# 03_HLT.net
KiCad netlist of a schematic drawn in EAGLE
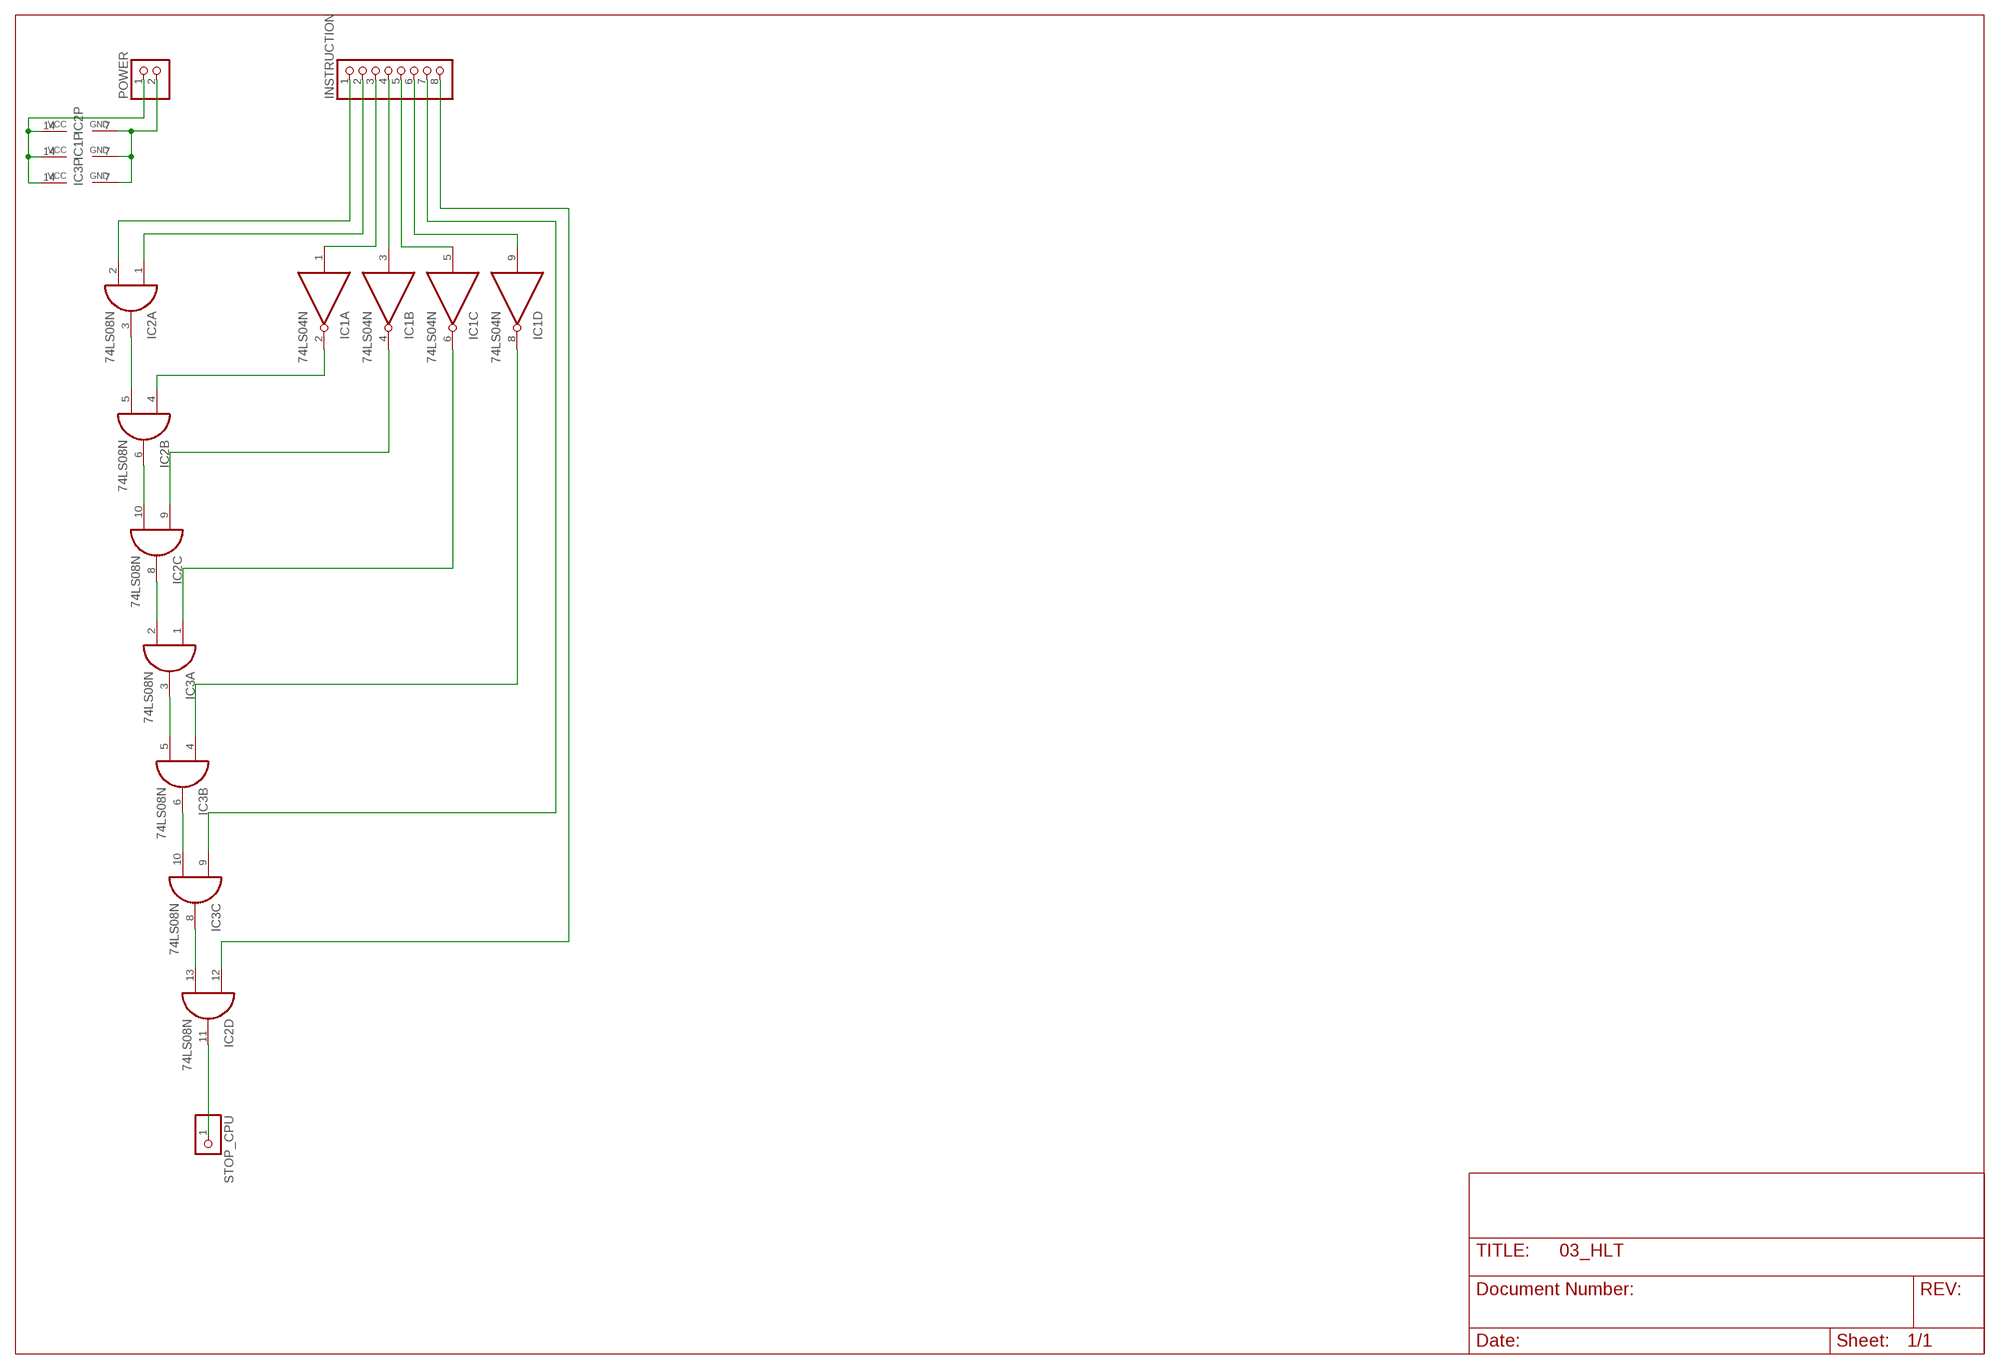
[diagram p0: schematic, sheet 1]

(export (version "E")
  (design (tool "Eeschema 10.0.6"))
  (components
    (comp (ref "IC1")
      (value "74LS04N")
      (footprint "eagle-import:DIL14")
      (libsource (lib "eagle-import") (part "7404NLS"))
    )
    (comp (ref "IC2")
      (value "74LS08N")
      (footprint "eagle-import:DIL14")
      (libsource (lib "eagle-import") (part "7408NLS"))
    )
    (comp (ref "IC3")
      (value "74LS08N")
      (footprint "eagle-import:DIL14")
      (libsource (lib "eagle-import") (part "7408NLS"))
    )
    (comp (ref "INSTRUCTION")
      (value "PINHD-1X8")
      (footprint "eagle-import:1X08")
      (libsource (lib "eagle-import") (part "PINHD-1X8"))
    )
    (comp (ref "POWER")
      (value "PINHD-1X2")
      (footprint "eagle-import:1X02")
      (libsource (lib "eagle-import") (part "PINHD-1X2"))
    )
    (comp (ref "STOP_CPU")
      (value "PINHD-1X1")
      (footprint "eagle-import:1X01")
      (libsource (lib "eagle-import") (part "PINHD-1X1"))
    )
  )
  (nets
    (net (code "1") (name "Net-(IC1A-I)") (class "Default")
      (node (ref "IC1") (pin "1") (pinfunction "I_1") (pintype "input"))
      (node (ref "INSTRUCTION") (pin "3") (pinfunction "3_3") (pintype "passive"))
    )
    (net (code "2") (name "Net-(IC1A-O)") (class "Default")
      (node (ref "IC1") (pin "2") (pinfunction "O_2") (pintype "output"))
      (node (ref "IC2") (pin "4") (pinfunction "I0_4") (pintype "input"))
    )
    (net (code "3") (name "Net-(IC1B-I)") (class "Default")
      (node (ref "IC1") (pin "3") (pinfunction "I_3") (pintype "input"))
      (node (ref "INSTRUCTION") (pin "4") (pinfunction "4_4") (pintype "passive"))
    )
    (net (code "4") (name "Net-(IC1B-O)") (class "Default")
      (node (ref "IC1") (pin "4") (pinfunction "O_4") (pintype "output"))
      (node (ref "IC2") (pin "9") (pinfunction "I0_9") (pintype "input"))
    )
    (net (code "5") (name "Net-(IC1C-I)") (class "Default")
      (node (ref "IC1") (pin "5") (pinfunction "I_5") (pintype "input"))
      (node (ref "INSTRUCTION") (pin "5") (pinfunction "5_5") (pintype "passive"))
    )
    (net (code "6") (name "Net-(IC1C-O)") (class "Default")
      (node (ref "IC1") (pin "6") (pinfunction "O_6") (pintype "output"))
      (node (ref "IC3") (pin "1") (pinfunction "I0_1") (pintype "input"))
    )
    (net (code "7") (name "Net-(IC1D-I)") (class "Default")
      (node (ref "IC1") (pin "9") (pinfunction "I_9") (pintype "input"))
      (node (ref "INSTRUCTION") (pin "6") (pinfunction "6_6") (pintype "passive"))
    )
    (net (code "8") (name "Net-(IC1D-O)") (class "Default")
      (node (ref "IC1") (pin "8") (pinfunction "O_8") (pintype "output"))
      (node (ref "IC3") (pin "4") (pinfunction "I0_4") (pintype "input"))
    )
    (net (code "9") (name "Net-(IC1G-GND)") (class "Default")
      (node (ref "IC1") (pin "7") (pinfunction "GND_7") (pintype "power_in"))
      (node (ref "IC2") (pin "7") (pinfunction "GND_7") (pintype "power_in"))
      (node (ref "IC3") (pin "7") (pinfunction "GND_7") (pintype "power_in"))
      (node (ref "POWER") (pin "2") (pinfunction "2_2") (pintype "passive"))
    )
    (net (code "10") (name "Net-(IC1G-VCC)") (class "Default")
      (node (ref "IC1") (pin "14") (pinfunction "VCC_14") (pintype "power_in"))
      (node (ref "IC2") (pin "14") (pinfunction "VCC_14") (pintype "power_in"))
      (node (ref "IC3") (pin "14") (pinfunction "VCC_14") (pintype "power_in"))
      (node (ref "POWER") (pin "1") (pinfunction "1_1") (pintype "passive"))
    )
    (net (code "11") (name "Net-(IC2A-I0)") (class "Default")
      (node (ref "IC2") (pin "1") (pinfunction "I0_1") (pintype "input"))
      (node (ref "INSTRUCTION") (pin "2") (pinfunction "2_2") (pintype "passive"))
    )
    (net (code "12") (name "Net-(IC2A-I1)") (class "Default")
      (node (ref "IC2") (pin "2") (pinfunction "I1_2") (pintype "input"))
      (node (ref "INSTRUCTION") (pin "1") (pinfunction "1_1") (pintype "passive"))
    )
    (net (code "13") (name "Net-(IC2A-O)") (class "Default")
      (node (ref "IC2") (pin "3") (pinfunction "O_3") (pintype "output"))
      (node (ref "IC2") (pin "5") (pinfunction "I1_5") (pintype "input"))
    )
    (net (code "14") (name "Net-(IC2B-O)") (class "Default")
      (node (ref "IC2") (pin "10") (pinfunction "I1_10") (pintype "input"))
      (node (ref "IC2") (pin "6") (pinfunction "O_6") (pintype "output"))
    )
    (net (code "15") (name "Net-(IC2C-O)") (class "Default")
      (node (ref "IC2") (pin "8") (pinfunction "O_8") (pintype "output"))
      (node (ref "IC3") (pin "2") (pinfunction "I1_2") (pintype "input"))
    )
    (net (code "16") (name "Net-(IC2D-I0)") (class "Default")
      (node (ref "IC2") (pin "12") (pinfunction "I0_12") (pintype "input"))
      (node (ref "INSTRUCTION") (pin "8") (pinfunction "8_8") (pintype "passive"))
    )
    (net (code "17") (name "Net-(IC2D-I1)") (class "Default")
      (node (ref "IC2") (pin "13") (pinfunction "I1_13") (pintype "input"))
      (node (ref "IC3") (pin "8") (pinfunction "O_8") (pintype "output"))
    )
    (net (code "18") (name "Net-(IC2D-O)") (class "Default")
      (node (ref "IC2") (pin "11") (pinfunction "O_11") (pintype "output"))
      (node (ref "STOP_CPU") (pin "1") (pinfunction "1_1") (pintype "passive"))
    )
    (net (code "19") (name "Net-(IC3A-O)") (class "Default")
      (node (ref "IC3") (pin "3") (pinfunction "O_3") (pintype "output"))
      (node (ref "IC3") (pin "5") (pinfunction "I1_5") (pintype "input"))
    )
    (net (code "20") (name "Net-(IC3B-O)") (class "Default")
      (node (ref "IC3") (pin "10") (pinfunction "I1_10") (pintype "input"))
      (node (ref "IC3") (pin "6") (pinfunction "O_6") (pintype "output"))
    )
    (net (code "21") (name "Net-(IC3C-I0)") (class "Default")
      (node (ref "IC3") (pin "9") (pinfunction "I0_9") (pintype "input"))
      (node (ref "INSTRUCTION") (pin "7") (pinfunction "7_7") (pintype "passive"))
    )
  )
)
